# esp8266-beacon.net
KiCad netlist of a schematic drawn in EAGLE
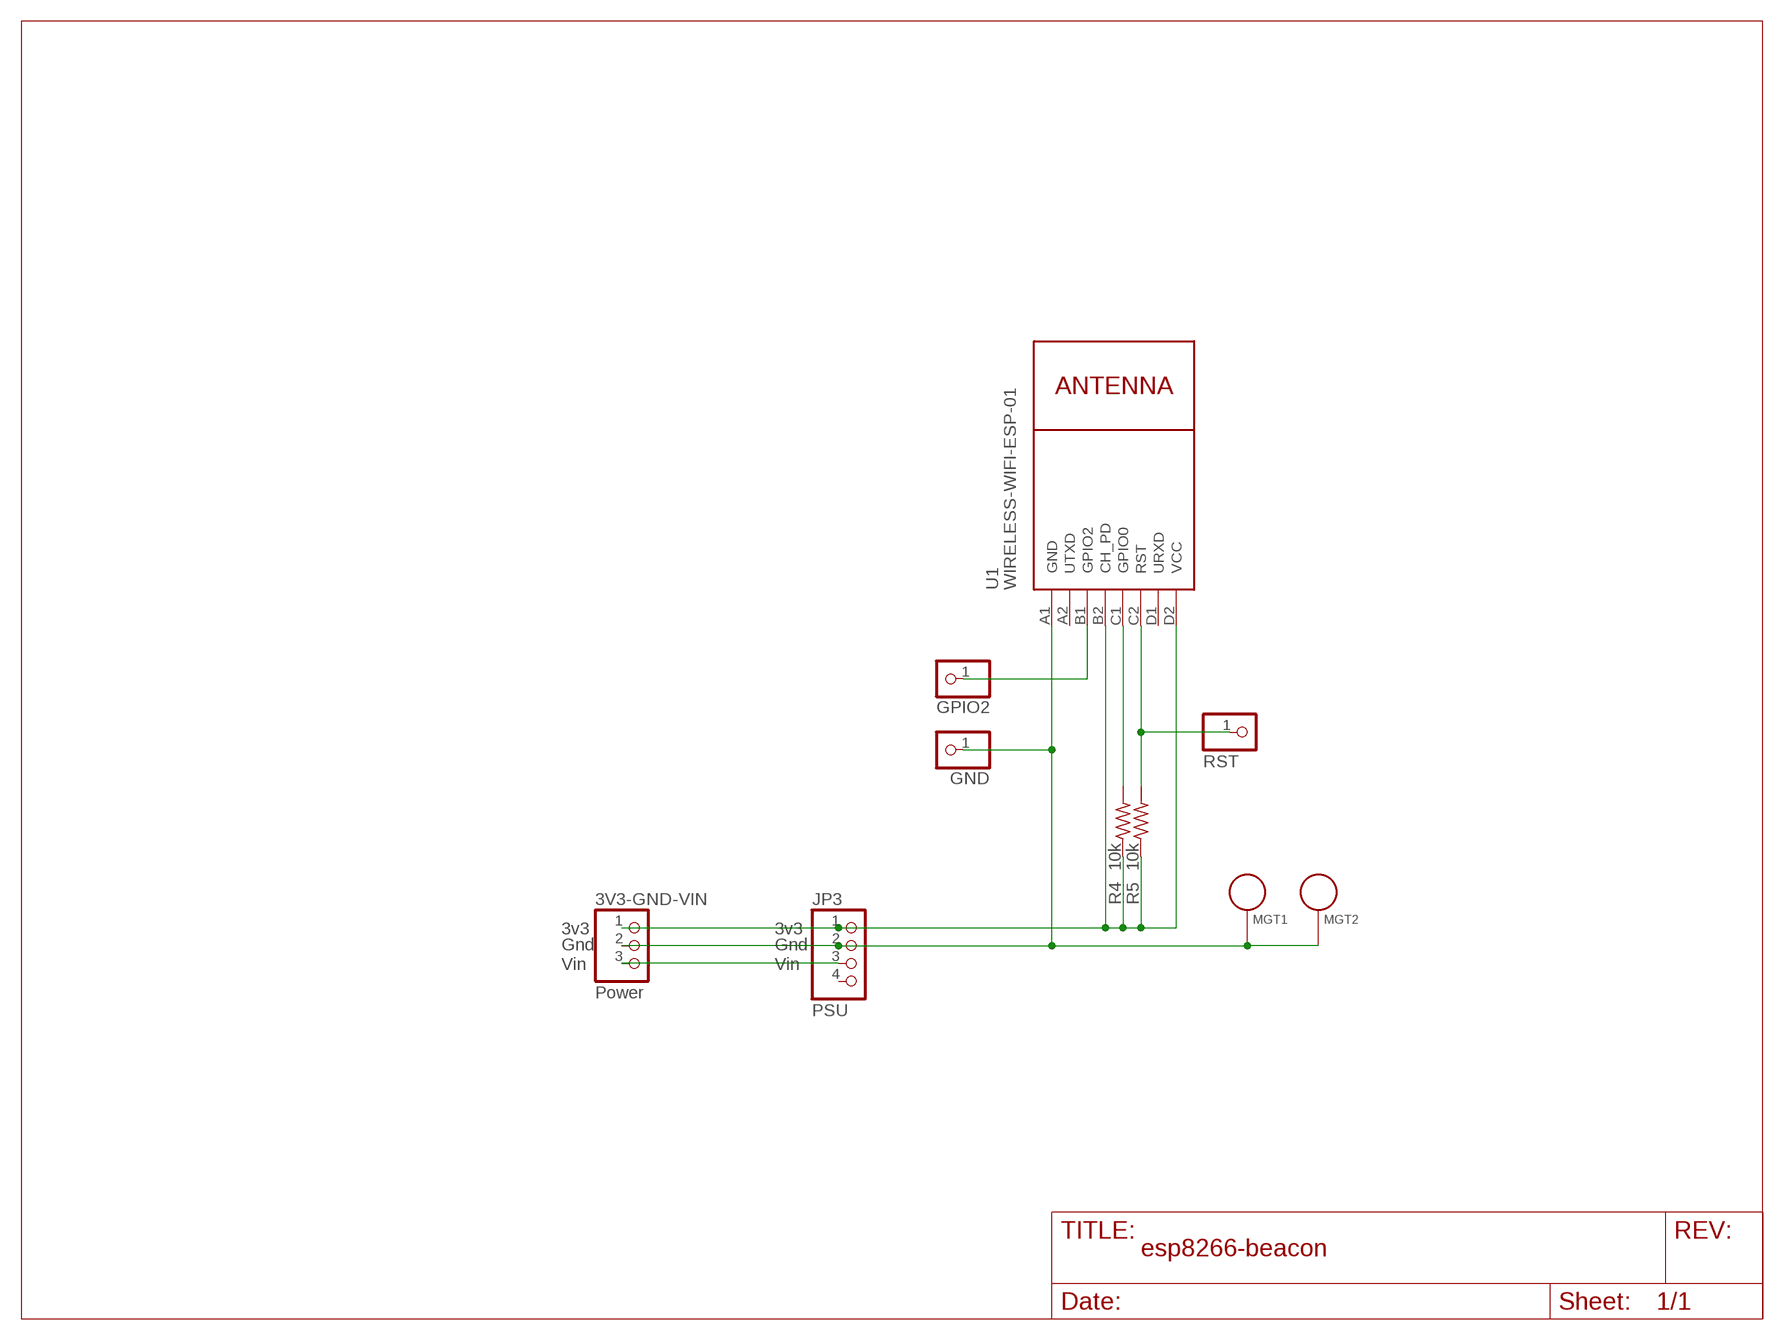
[diagram p0: schematic, sheet 1]

(export (version "E")
  (design (tool "Eeschema 10.0.6"))
  (components
    (comp (ref "3V3-GND-VIN")
      (value "Power")
      (footprint "eagle-import:1X03")
      (libsource (lib "eagle-import") (part "PINHD-1X3"))
    )
    (comp (ref "GND")
      (value "RST")
      (footprint "eagle-import:1X01")
      (libsource (lib "eagle-import") (part "PINHD-1X1"))
    )
    (comp (ref "GPIO2")
      (value "RST")
      (footprint "eagle-import:1X01")
      (libsource (lib "eagle-import") (part "PINHD-1X1"))
    )
    (comp (ref "JP3")
      (value "PSU")
      (footprint "eagle-import:1X04")
      (libsource (lib "eagle-import") (part "PINHD-1X4"))
    )
    (comp (ref "MGT1")
      (value "BEAGLEBONEBLACK_MOUNTING_HOLE")
      (footprint "eagle-import:BEAGLEBONEBLACK_MOUNTING_HOLE")
      (libsource (lib "eagle-import") (part "BEAGLEBONEBLACK_MOUNTING_HOLE"))
    )
    (comp (ref "MGT2")
      (value "BEAGLEBONEBLACK_MOUNTING_HOLE")
      (footprint "eagle-import:BEAGLEBONEBLACK_MOUNTING_HOLE")
      (libsource (lib "eagle-import") (part "BEAGLEBONEBLACK_MOUNTING_HOLE"))
    )
    (comp (ref "R4")
      (value "10k")
      (footprint "eagle-import:0207_10")
      (libsource (lib "eagle-import") (part "R-US_0207/10"))
    )
    (comp (ref "R5")
      (value "10k")
      (footprint "eagle-import:0207_10")
      (libsource (lib "eagle-import") (part "R-US_0207/10"))
    )
    (comp (ref "RST")
      (value "RST")
      (footprint "eagle-import:1X01")
      (libsource (lib "eagle-import") (part "PINHD-1X1"))
    )
    (comp (ref "U1")
      (value "WIRELESS-WIFI-ESP-01")
      (footprint "eagle-import:WIRELESS-WIFI-ESP-01")
      (libsource (lib "eagle-import") (part "WIRELESS-WIFI-ESP-01"))
    )
  )
  (nets
    (net (code "1") (name "Net-(3V3-GND-VIN-Pad3)") (class "Default")
      (node (ref "3V3-GND-VIN") (pin "3") (pinfunction "3_3") (pintype "passive"))
      (node (ref "JP3") (pin "3") (pinfunction "3_3") (pintype "passive"))
    )
    (net (code "2") (name "Net-(U1-CH_PD)") (class "Default")
      (node (ref "3V3-GND-VIN") (pin "1") (pinfunction "1_1") (pintype "passive"))
      (node (ref "JP3") (pin "1") (pinfunction "1_1") (pintype "passive"))
      (node (ref "R4") (pin "1") (pinfunction "1_1") (pintype "passive"))
      (node (ref "R5") (pin "1") (pinfunction "1_1") (pintype "passive"))
      (node (ref "U1") (pin "B2") (pinfunction "CH_PD_B2") (pintype "bidirectional"))
      (node (ref "U1") (pin "D2") (pinfunction "VCC_D2") (pintype "power_in"))
    )
    (net (code "3") (name "Net-(U1-GND)") (class "Default")
      (node (ref "3V3-GND-VIN") (pin "2") (pinfunction "2_2") (pintype "passive"))
      (node (ref "GND") (pin "1") (pinfunction "1_1") (pintype "passive"))
      (node (ref "JP3") (pin "2") (pinfunction "2_2") (pintype "passive"))
      (node (ref "MGT1") (pin "P$1") (pinfunction "P$1_P$1") (pintype "bidirectional"))
      (node (ref "MGT2") (pin "P$1") (pinfunction "P$1_P$1") (pintype "bidirectional"))
      (node (ref "U1") (pin "A1") (pinfunction "GND_A1") (pintype "power_in"))
    )
    (net (code "4") (name "Net-(U1-GPIO0)") (class "Default")
      (node (ref "R4") (pin "2") (pinfunction "2_2") (pintype "passive"))
      (node (ref "U1") (pin "C1") (pinfunction "GPIO0_C1") (pintype "bidirectional"))
    )
    (net (code "5") (name "Net-(U1-GPIO2)") (class "Default")
      (node (ref "GPIO2") (pin "1") (pinfunction "1_1") (pintype "passive"))
      (node (ref "U1") (pin "B1") (pinfunction "GPIO2_B1") (pintype "bidirectional"))
    )
    (net (code "6") (name "Net-(U1-RST)") (class "Default")
      (node (ref "R5") (pin "2") (pinfunction "2_2") (pintype "passive"))
      (node (ref "RST") (pin "1") (pinfunction "1_1") (pintype "passive"))
      (node (ref "U1") (pin "C2") (pinfunction "RST_C2") (pintype "bidirectional"))
    )
    (net (code "7") (name "unconnected-(JP3-Pad4)") (class "Default")
      (node (ref "JP3") (pin "4") (pinfunction "4_4") (pintype "passive"))
    )
    (net (code "8") (name "unconnected-(U1-URXD-PadD1)") (class "Default")
      (node (ref "U1") (pin "D1") (pinfunction "URXD_D1") (pintype "bidirectional"))
    )
    (net (code "9") (name "unconnected-(U1-UTXD-PadA2)") (class "Default")
      (node (ref "U1") (pin "A2") (pinfunction "UTXD_A2") (pintype "bidirectional"))
    )
  )
)
